# schema_eletrico_PED.net
KiCad netlist of a schematic drawn in EasyEDA
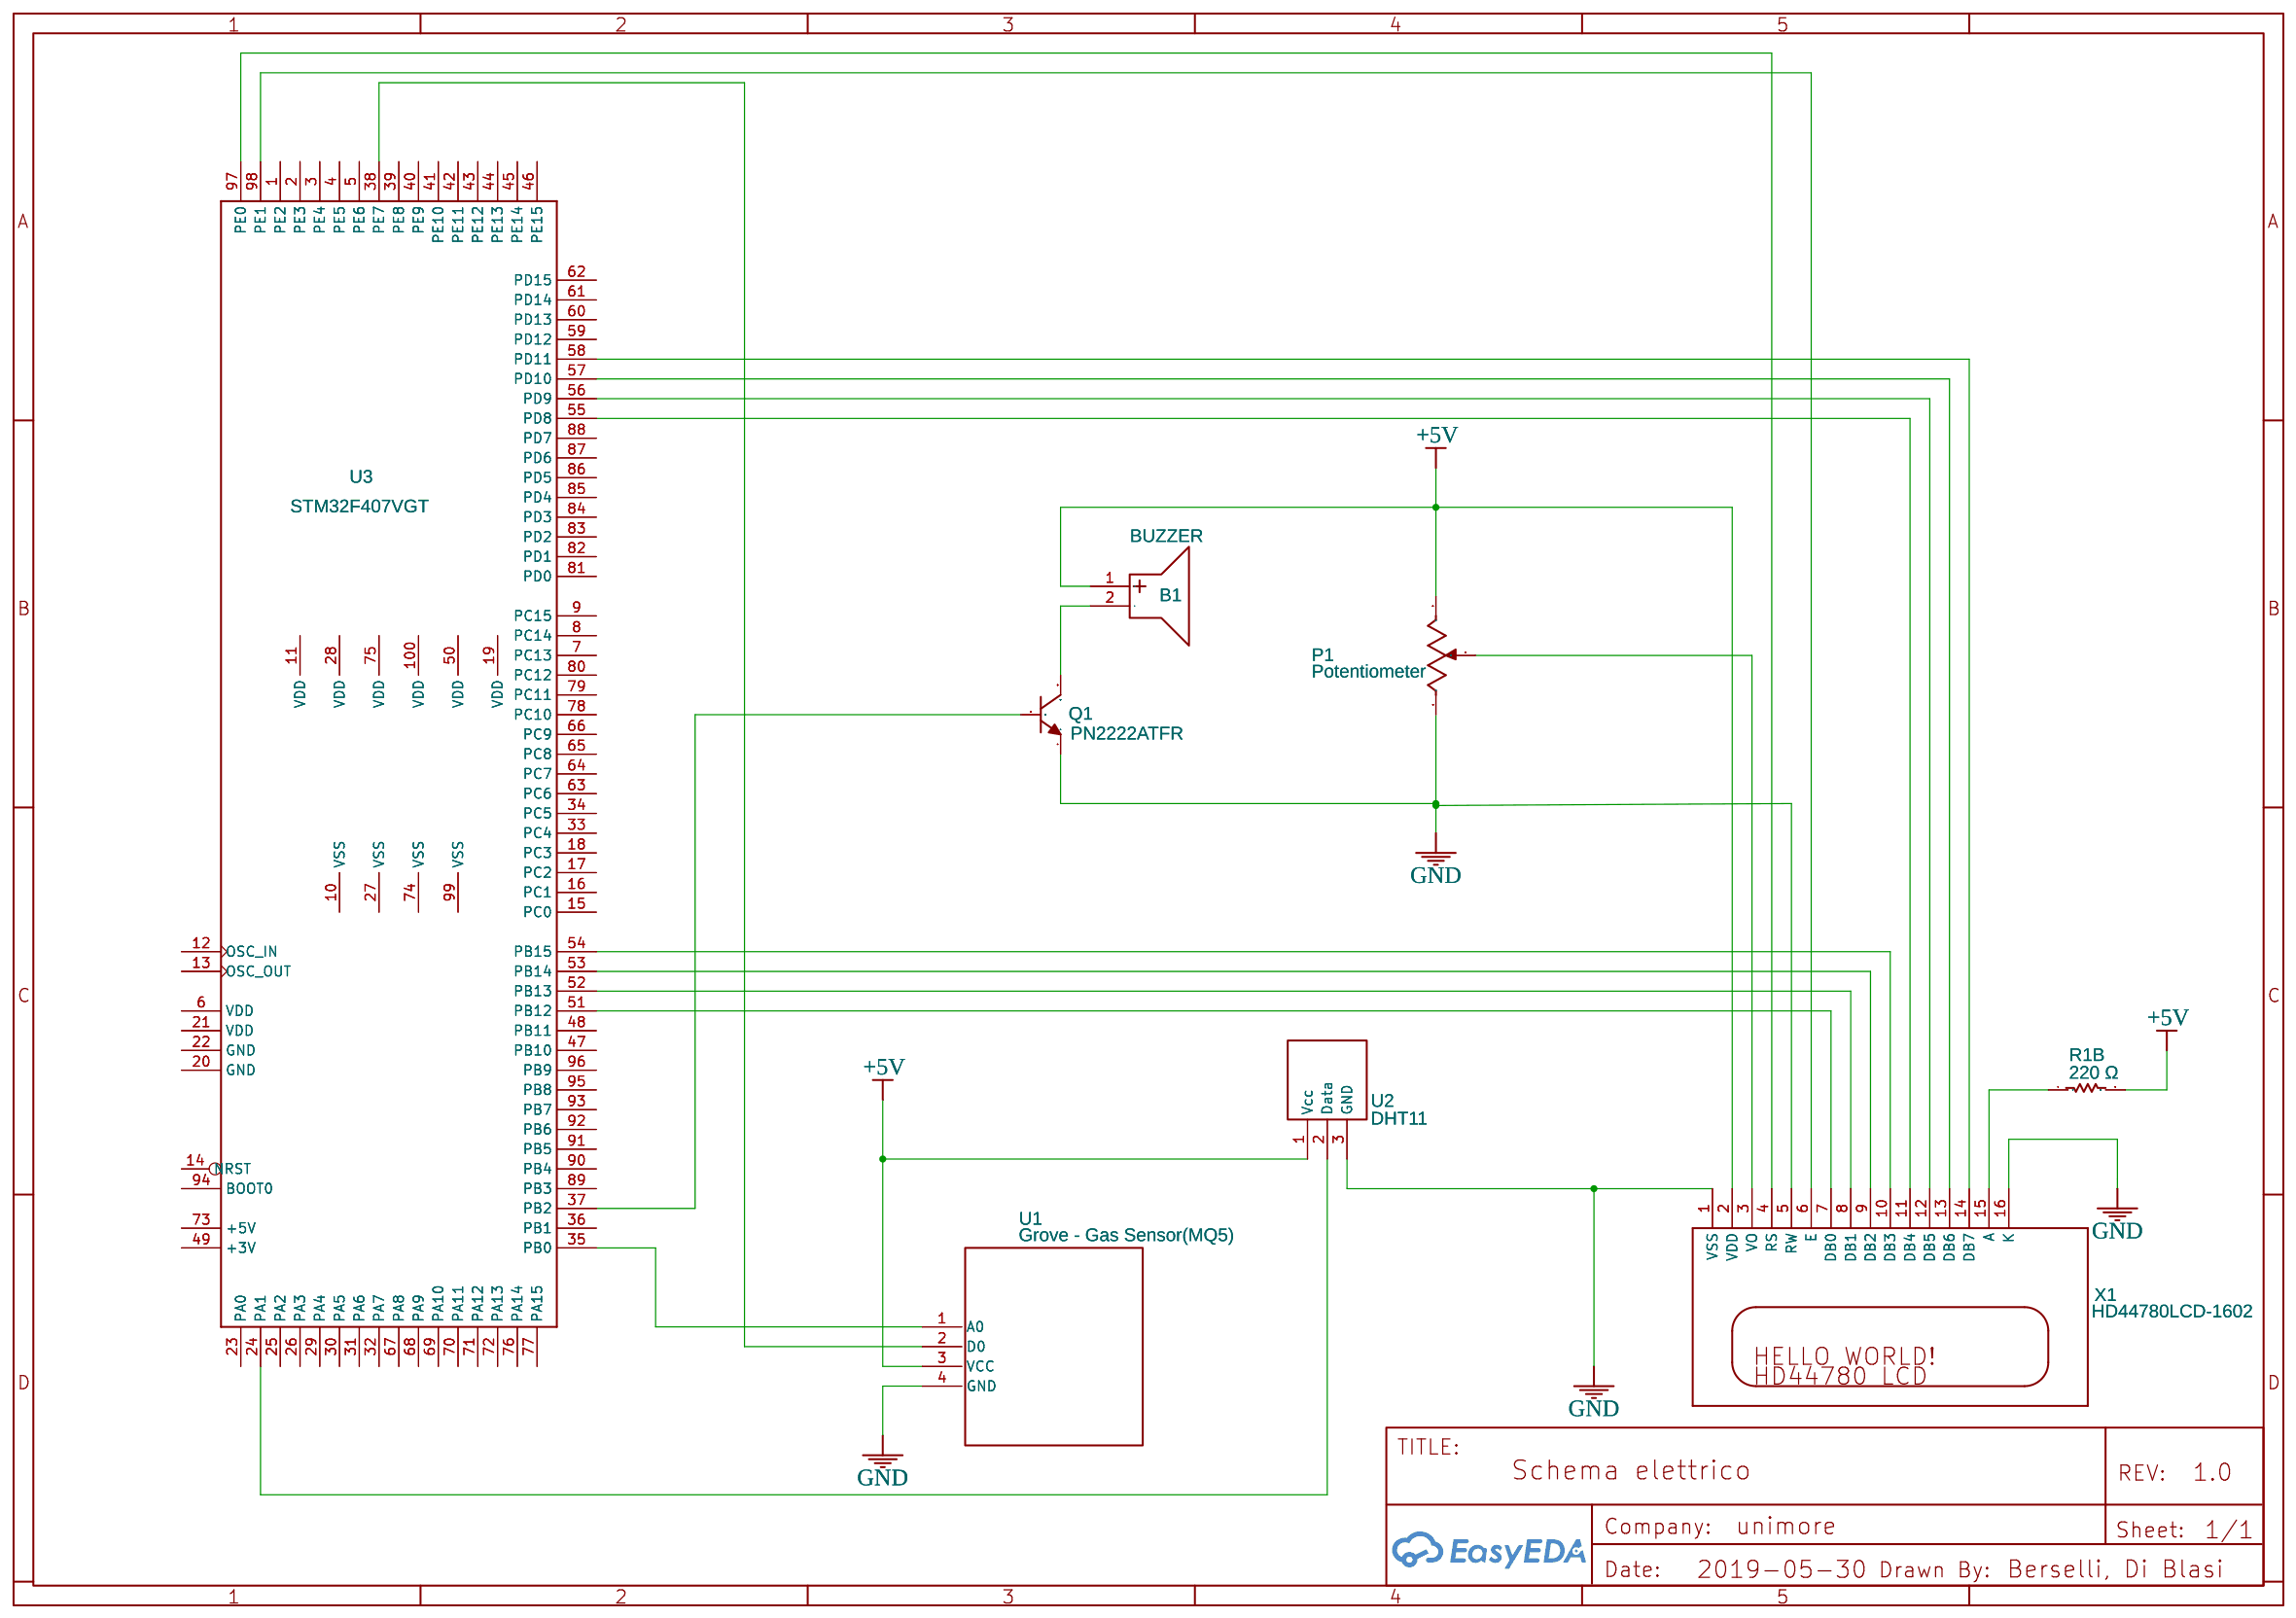
[diagram p0: schematic sheet]

(export (version "E")
  (design (tool "Eeschema 10.0.6"))
  (components
    (comp (ref "B1")
      (value "BUZZER")
      (fields
        (field (name "BOM_Manufacturer Part") "BL-PBZ1209C2003YB-H")
        (field (name "BOM_Supplier Part") "C187885")
      )
      (libsource (lib "") (part "Unknown_575_300"))
    )
    (comp (ref "P1")
      (value "Potentiometer")
      (fields (field (name "BOM_Manufacturer Part") "?"))
      (libsource (lib "") (part "Unknown_720_325"))
    )
    (comp (ref "Q1")
      (value "PN2222ATFR")
      (fields (field (name "BOM_Supplier Part") "C184875"))
      (libsource (lib "") (part "Unknown_520_355"))
    )
    (comp (ref "R1B")
      (value "220 Ω")
      (fields (field (name "BOM_Manufacturer Part") "?") (field (name "BOM_Supplier Part") "P100KHCT-ND"))
      (libsource (lib "") (part "Unknown_1045_545"))
    )
    (comp (ref "U1")
      (value "Grove - Gas Sensor(MQ5)")
      (fields (field (name "BOM_Manufacturer Part") "?") (field (name "BOM_Supplier Part") "undefined"))
      (libsource (lib "") (part "Unknown_515_675"))
    )
    (comp (ref "U2") (value "DHT11") (libsource (lib "") (part "Unknown_725_550")))
    (comp (ref "U3")
      (value "STM32F407VGT")
      (fields (field (name "BOM_Manufacturer Part") "?"))
      (libsource (lib "") (part "Unknown_190_380"))
    )
    (comp (ref "X1")
      (value "HD44780LCD-1602")
      (fields (field (name "BOM_Manufacturer Part") "?"))
      (libsource (lib "") (part "Unknown_950_650"))
    )
  )
  (nets
    (net (code "1") (name "+5V") (class "Default")
      (node (ref "B1") (pin "1") (pinfunction "+_1") (pintype "unspecified"))
      (node (ref "P1") (pin "2") (pinfunction "E_2") (pintype "unspecified"))
      (node (ref "R1B") (pin "2") (pinfunction "2_2") (pintype "passive"))
      (node (ref "U1") (pin "3") (pinfunction "VCC_3") (pintype "unspecified"))
      (node (ref "U2") (pin "1") (pinfunction "Vcc_1") (pintype "unspecified"))
      (node (ref "X1") (pin "2") (pinfunction "VDD_2") (pintype "unspecified"))
    )
    (net (code "2") (name "GND") (class "Default")
      (node (ref "P1") (pin "3") (pinfunction "A_3") (pintype "unspecified"))
      (node (ref "Q1") (pin "1") (pinfunction "E_1") (pintype "unspecified"))
      (node (ref "U1") (pin "4") (pinfunction "GND_4") (pintype "unspecified"))
      (node (ref "U2") (pin "3") (pinfunction "GND_3") (pintype "unspecified"))
      (node (ref "X1") (pin "1") (pinfunction "VSS_1") (pintype "unspecified"))
      (node (ref "X1") (pin "16") (pinfunction "K_16") (pintype "input"))
      (node (ref "X1") (pin "5") (pinfunction "RW_5") (pintype "input"))
    )
    (net (code "3") (name "Net-(B1--)") (class "Default")
      (node (ref "B1") (pin "2") (pinfunction "-_2") (pintype "unspecified"))
      (node (ref "Q1") (pin "3") (pinfunction "C_3") (pintype "unspecified"))
    )
    (net (code "4") (name "Net-(P1-S)") (class "Default")
      (node (ref "P1") (pin "1") (pinfunction "S_1") (pintype "unspecified"))
      (node (ref "X1") (pin "3") (pinfunction "VO_3") (pintype "input"))
    )
    (net (code "5") (name "Net-(Q1-B)") (class "Default")
      (node (ref "Q1") (pin "2") (pinfunction "B_2") (pintype "unspecified"))
      (node (ref "U3") (pin "37") (pinfunction "PB2_37") (pintype "unspecified"))
    )
    (net (code "6") (name "Net-(U1-A0)") (class "Default")
      (node (ref "U1") (pin "1") (pinfunction "A0_1") (pintype "unspecified"))
      (node (ref "U3") (pin "35") (pinfunction "PB0_35") (pintype "unspecified"))
    )
    (net (code "7") (name "Net-(U1-D0)") (class "Default")
      (node (ref "U1") (pin "2") (pinfunction "D0_2") (pintype "unspecified"))
      (node (ref "U3") (pin "38") (pinfunction "PE7_38") (pintype "unspecified"))
    )
    (net (code "8") (name "Net-(U2-Data)") (class "Default")
      (node (ref "U2") (pin "2") (pinfunction "Data_2") (pintype "unspecified"))
      (node (ref "U3") (pin "24") (pinfunction "PA1_24") (pintype "unspecified"))
    )
    (net (code "9") (name "Net-(U3-PB12)") (class "Default")
      (node (ref "U3") (pin "51") (pinfunction "PB12_51") (pintype "unspecified"))
      (node (ref "X1") (pin "7") (pinfunction "DB0_7") (pintype "unspecified"))
    )
    (net (code "10") (name "Net-(U3-PB13)") (class "Default")
      (node (ref "U3") (pin "52") (pinfunction "PB13_52") (pintype "unspecified"))
      (node (ref "X1") (pin "8") (pinfunction "DB1_8") (pintype "unspecified"))
    )
    (net (code "11") (name "Net-(U3-PB14)") (class "Default")
      (node (ref "U3") (pin "53") (pinfunction "PB14_53") (pintype "unspecified"))
      (node (ref "X1") (pin "9") (pinfunction "DB2_9") (pintype "unspecified"))
    )
    (net (code "12") (name "Net-(U3-PB15)") (class "Default")
      (node (ref "U3") (pin "54") (pinfunction "PB15_54") (pintype "unspecified"))
      (node (ref "X1") (pin "10") (pinfunction "DB3_10") (pintype "unspecified"))
    )
    (net (code "13") (name "Net-(U3-PD8)") (class "Default")
      (node (ref "U3") (pin "55") (pinfunction "PD8_55") (pintype "unspecified"))
      (node (ref "X1") (pin "11") (pinfunction "DB4_11") (pintype "unspecified"))
    )
    (net (code "14") (name "Net-(U3-PD9)") (class "Default")
      (node (ref "U3") (pin "56") (pinfunction "PD9_56") (pintype "unspecified"))
      (node (ref "X1") (pin "12") (pinfunction "DB5_12") (pintype "unspecified"))
    )
    (net (code "15") (name "Net-(U3-PD10)") (class "Default")
      (node (ref "U3") (pin "57") (pinfunction "PD10_57") (pintype "unspecified"))
      (node (ref "X1") (pin "13") (pinfunction "DB6_13") (pintype "unspecified"))
    )
    (net (code "16") (name "Net-(U3-PD11)") (class "Default")
      (node (ref "U3") (pin "58") (pinfunction "PD11_58") (pintype "unspecified"))
      (node (ref "X1") (pin "14") (pinfunction "DB7_14") (pintype "unspecified"))
    )
    (net (code "17") (name "Net-(U3-PE0)") (class "Default")
      (node (ref "U3") (pin "97") (pinfunction "PE0_97") (pintype "unspecified"))
      (node (ref "X1") (pin "4") (pinfunction "RS_4") (pintype "input"))
    )
    (net (code "18") (name "Net-(U3-PE1)") (class "Default")
      (node (ref "U3") (pin "98") (pinfunction "PE1_98") (pintype "unspecified"))
      (node (ref "X1") (pin "6") (pinfunction "E_6") (pintype "input"))
    )
    (net (code "19") (name "Net-(X1-A)") (class "Default")
      (node (ref "R1B") (pin "1") (pinfunction "1_1") (pintype "passive"))
      (node (ref "X1") (pin "15") (pinfunction "A_15") (pintype "input"))
    )
    (net (code "20") (name "unconnected-(U3-+3V-Pad49)") (class "Default")
      (node (ref "U3") (pin "49") (pinfunction "+3V_49") (pintype "passive"))
    )
    (net (code "21") (name "unconnected-(U3-+5V-Pad73)") (class "Default")
      (node (ref "U3") (pin "73") (pinfunction "+5V_73") (pintype "passive"))
    )
    (net (code "22") (name "unconnected-(U3-BOOT0-Pad94)") (class "Default")
      (node (ref "U3") (pin "94") (pinfunction "BOOT0_94") (pintype "input"))
    )
    (net (code "23") (name "unconnected-(U3-GND-Pad20)") (class "Default")
      (node (ref "U3") (pin "20") (pinfunction "GND_20") (pintype "passive"))
    )
    (net (code "24") (name "unconnected-(U3-GND-Pad22)") (class "Default")
      (node (ref "U3") (pin "22") (pinfunction "GND_22") (pintype "passive"))
    )
    (net (code "25") (name "unconnected-(U3-NRST-Pad14)") (class "Default")
      (node (ref "U3") (pin "14") (pinfunction "NRST_14") (pintype "unspecified"))
    )
    (net (code "26") (name "unconnected-(U3-OSC_IN-Pad12)") (class "Default")
      (node (ref "U3") (pin "12") (pinfunction "OSC_IN_12") (pintype "unspecified"))
    )
    (net (code "27") (name "unconnected-(U3-OSC_OUT-Pad13)") (class "Default")
      (node (ref "U3") (pin "13") (pinfunction "OSC_OUT_13") (pintype "unspecified"))
    )
    (net (code "28") (name "unconnected-(U3-PA0-Pad23)") (class "Default")
      (node (ref "U3") (pin "23") (pinfunction "PA0_23") (pintype "unspecified"))
    )
    (net (code "29") (name "unconnected-(U3-PA2-Pad25)") (class "Default")
      (node (ref "U3") (pin "25") (pinfunction "PA2_25") (pintype "unspecified"))
    )
    (net (code "30") (name "unconnected-(U3-PA3-Pad26)") (class "Default")
      (node (ref "U3") (pin "26") (pinfunction "PA3_26") (pintype "unspecified"))
    )
    (net (code "31") (name "unconnected-(U3-PA4-Pad29)") (class "Default")
      (node (ref "U3") (pin "29") (pinfunction "PA4_29") (pintype "unspecified"))
    )
    (net (code "32") (name "unconnected-(U3-PA5-Pad30)") (class "Default")
      (node (ref "U3") (pin "30") (pinfunction "PA5_30") (pintype "unspecified"))
    )
    (net (code "33") (name "unconnected-(U3-PA6-Pad31)") (class "Default")
      (node (ref "U3") (pin "31") (pinfunction "PA6_31") (pintype "unspecified"))
    )
    (net (code "34") (name "unconnected-(U3-PA7-Pad32)") (class "Default")
      (node (ref "U3") (pin "32") (pinfunction "PA7_32") (pintype "unspecified"))
    )
    (net (code "35") (name "unconnected-(U3-PA8-Pad67)") (class "Default")
      (node (ref "U3") (pin "67") (pinfunction "PA8_67") (pintype "unspecified"))
    )
    (net (code "36") (name "unconnected-(U3-PA9-Pad68)") (class "Default")
      (node (ref "U3") (pin "68") (pinfunction "PA9_68") (pintype "unspecified"))
    )
    (net (code "37") (name "unconnected-(U3-PA10-Pad69)") (class "Default")
      (node (ref "U3") (pin "69") (pinfunction "PA10_69") (pintype "unspecified"))
    )
    (net (code "38") (name "unconnected-(U3-PA11-Pad70)") (class "Default")
      (node (ref "U3") (pin "70") (pinfunction "PA11_70") (pintype "unspecified"))
    )
    (net (code "39") (name "unconnected-(U3-PA12-Pad71)") (class "Default")
      (node (ref "U3") (pin "71") (pinfunction "PA12_71") (pintype "unspecified"))
    )
    (net (code "40") (name "unconnected-(U3-PA13-Pad72)") (class "Default")
      (node (ref "U3") (pin "72") (pinfunction "PA13_72") (pintype "unspecified"))
    )
    (net (code "41") (name "unconnected-(U3-PA14-Pad76)") (class "Default")
      (node (ref "U3") (pin "76") (pinfunction "PA14_76") (pintype "unspecified"))
    )
    (net (code "42") (name "unconnected-(U3-PA15-Pad77)") (class "Default")
      (node (ref "U3") (pin "77") (pinfunction "PA15_77") (pintype "unspecified"))
    )
    (net (code "43") (name "unconnected-(U3-PB1-Pad36)") (class "Default")
      (node (ref "U3") (pin "36") (pinfunction "PB1_36") (pintype "unspecified"))
    )
    (net (code "44") (name "unconnected-(U3-PB3-Pad89)") (class "Default")
      (node (ref "U3") (pin "89") (pinfunction "PB3_89") (pintype "unspecified"))
    )
    (net (code "45") (name "unconnected-(U3-PB4-Pad90)") (class "Default")
      (node (ref "U3") (pin "90") (pinfunction "PB4_90") (pintype "unspecified"))
    )
    (net (code "46") (name "unconnected-(U3-PB5-Pad91)") (class "Default")
      (node (ref "U3") (pin "91") (pinfunction "PB5_91") (pintype "unspecified"))
    )
    (net (code "47") (name "unconnected-(U3-PB6-Pad92)") (class "Default")
      (node (ref "U3") (pin "92") (pinfunction "PB6_92") (pintype "unspecified"))
    )
    (net (code "48") (name "unconnected-(U3-PB7-Pad93)") (class "Default")
      (node (ref "U3") (pin "93") (pinfunction "PB7_93") (pintype "unspecified"))
    )
    (net (code "49") (name "unconnected-(U3-PB8-Pad95)") (class "Default")
      (node (ref "U3") (pin "95") (pinfunction "PB8_95") (pintype "unspecified"))
    )
    (net (code "50") (name "unconnected-(U3-PB9-Pad96)") (class "Default")
      (node (ref "U3") (pin "96") (pinfunction "PB9_96") (pintype "unspecified"))
    )
    (net (code "51") (name "unconnected-(U3-PB10-Pad47)") (class "Default")
      (node (ref "U3") (pin "47") (pinfunction "PB10_47") (pintype "unspecified"))
    )
    (net (code "52") (name "unconnected-(U3-PB11-Pad48)") (class "Default")
      (node (ref "U3") (pin "48") (pinfunction "PB11_48") (pintype "unspecified"))
    )
    (net (code "53") (name "unconnected-(U3-PC0-Pad15)") (class "Default")
      (node (ref "U3") (pin "15") (pinfunction "PC0_15") (pintype "unspecified"))
    )
    (net (code "54") (name "unconnected-(U3-PC1-Pad16)") (class "Default")
      (node (ref "U3") (pin "16") (pinfunction "PC1_16") (pintype "unspecified"))
    )
    (net (code "55") (name "unconnected-(U3-PC2-Pad17)") (class "Default")
      (node (ref "U3") (pin "17") (pinfunction "PC2_17") (pintype "unspecified"))
    )
    (net (code "56") (name "unconnected-(U3-PC3-Pad18)") (class "Default")
      (node (ref "U3") (pin "18") (pinfunction "PC3_18") (pintype "unspecified"))
    )
    (net (code "57") (name "unconnected-(U3-PC4-Pad33)") (class "Default")
      (node (ref "U3") (pin "33") (pinfunction "PC4_33") (pintype "unspecified"))
    )
    (net (code "58") (name "unconnected-(U3-PC5-Pad34)") (class "Default")
      (node (ref "U3") (pin "34") (pinfunction "PC5_34") (pintype "unspecified"))
    )
    (net (code "59") (name "unconnected-(U3-PC6-Pad63)") (class "Default")
      (node (ref "U3") (pin "63") (pinfunction "PC6_63") (pintype "unspecified"))
    )
    (net (code "60") (name "unconnected-(U3-PC7-Pad64)") (class "Default")
      (node (ref "U3") (pin "64") (pinfunction "PC7_64") (pintype "unspecified"))
    )
    (net (code "61") (name "unconnected-(U3-PC8-Pad65)") (class "Default")
      (node (ref "U3") (pin "65") (pinfunction "PC8_65") (pintype "unspecified"))
    )
    (net (code "62") (name "unconnected-(U3-PC9-Pad66)") (class "Default")
      (node (ref "U3") (pin "66") (pinfunction "PC9_66") (pintype "unspecified"))
    )
    (net (code "63") (name "unconnected-(U3-PC10-Pad78)") (class "Default")
      (node (ref "U3") (pin "78") (pinfunction "PC10_78") (pintype "unspecified"))
    )
    (net (code "64") (name "unconnected-(U3-PC11-Pad79)") (class "Default")
      (node (ref "U3") (pin "79") (pinfunction "PC11_79") (pintype "unspecified"))
    )
    (net (code "65") (name "unconnected-(U3-PC12-Pad80)") (class "Default")
      (node (ref "U3") (pin "80") (pinfunction "PC12_80") (pintype "unspecified"))
    )
    (net (code "66") (name "unconnected-(U3-PC13-Pad7)") (class "Default")
      (node (ref "U3") (pin "7") (pinfunction "PC13_7") (pintype "unspecified"))
    )
    (net (code "67") (name "unconnected-(U3-PC14-Pad8)") (class "Default")
      (node (ref "U3") (pin "8") (pinfunction "PC14_8") (pintype "unspecified"))
    )
    (net (code "68") (name "unconnected-(U3-PC15-Pad9)") (class "Default")
      (node (ref "U3") (pin "9") (pinfunction "PC15_9") (pintype "unspecified"))
    )
    (net (code "69") (name "unconnected-(U3-PD0-Pad81)") (class "Default")
      (node (ref "U3") (pin "81") (pinfunction "PD0_81") (pintype "unspecified"))
    )
    (net (code "70") (name "unconnected-(U3-PD1-Pad82)") (class "Default")
      (node (ref "U3") (pin "82") (pinfunction "PD1_82") (pintype "unspecified"))
    )
    (net (code "71") (name "unconnected-(U3-PD2-Pad83)") (class "Default")
      (node (ref "U3") (pin "83") (pinfunction "PD2_83") (pintype "unspecified"))
    )
    (net (code "72") (name "unconnected-(U3-PD3-Pad84)") (class "Default")
      (node (ref "U3") (pin "84") (pinfunction "PD3_84") (pintype "unspecified"))
    )
    (net (code "73") (name "unconnected-(U3-PD4-Pad85)") (class "Default")
      (node (ref "U3") (pin "85") (pinfunction "PD4_85") (pintype "unspecified"))
    )
    (net (code "74") (name "unconnected-(U3-PD5-Pad86)") (class "Default")
      (node (ref "U3") (pin "86") (pinfunction "PD5_86") (pintype "unspecified"))
    )
    (net (code "75") (name "unconnected-(U3-PD6-Pad87)") (class "Default")
      (node (ref "U3") (pin "87") (pinfunction "PD6_87") (pintype "unspecified"))
    )
    (net (code "76") (name "unconnected-(U3-PD7-Pad88)") (class "Default")
      (node (ref "U3") (pin "88") (pinfunction "PD7_88") (pintype "unspecified"))
    )
    (net (code "77") (name "unconnected-(U3-PD12-Pad59)") (class "Default")
      (node (ref "U3") (pin "59") (pinfunction "PD12_59") (pintype "unspecified"))
    )
    (net (code "78") (name "unconnected-(U3-PD13-Pad60)") (class "Default")
      (node (ref "U3") (pin "60") (pinfunction "PD13_60") (pintype "unspecified"))
    )
    (net (code "79") (name "unconnected-(U3-PD14-Pad61)") (class "Default")
      (node (ref "U3") (pin "61") (pinfunction "PD14_61") (pintype "unspecified"))
    )
    (net (code "80") (name "unconnected-(U3-PD15-Pad62)") (class "Default")
      (node (ref "U3") (pin "62") (pinfunction "PD15_62") (pintype "unspecified"))
    )
    (net (code "81") (name "unconnected-(U3-PE2-Pad1)") (class "Default")
      (node (ref "U3") (pin "1") (pinfunction "PE2_1") (pintype "unspecified"))
    )
    (net (code "82") (name "unconnected-(U3-PE3-Pad2)") (class "Default")
      (node (ref "U3") (pin "2") (pinfunction "PE3_2") (pintype "unspecified"))
    )
    (net (code "83") (name "unconnected-(U3-PE4-Pad3)") (class "Default")
      (node (ref "U3") (pin "3") (pinfunction "PE4_3") (pintype "unspecified"))
    )
    (net (code "84") (name "unconnected-(U3-PE5-Pad4)") (class "Default")
      (node (ref "U3") (pin "4") (pinfunction "PE5_4") (pintype "unspecified"))
    )
    (net (code "85") (name "unconnected-(U3-PE6-Pad5)") (class "Default")
      (node (ref "U3") (pin "5") (pinfunction "PE6_5") (pintype "unspecified"))
    )
    (net (code "86") (name "unconnected-(U3-PE8-Pad39)") (class "Default")
      (node (ref "U3") (pin "39") (pinfunction "PE8_39") (pintype "unspecified"))
    )
    (net (code "87") (name "unconnected-(U3-PE9-Pad40)") (class "Default")
      (node (ref "U3") (pin "40") (pinfunction "PE9_40") (pintype "unspecified"))
    )
    (net (code "88") (name "unconnected-(U3-PE10-Pad41)") (class "Default")
      (node (ref "U3") (pin "41") (pinfunction "PE10_41") (pintype "unspecified"))
    )
    (net (code "89") (name "unconnected-(U3-PE11-Pad42)") (class "Default")
      (node (ref "U3") (pin "42") (pinfunction "PE11_42") (pintype "unspecified"))
    )
    (net (code "90") (name "unconnected-(U3-PE12-Pad43)") (class "Default")
      (node (ref "U3") (pin "43") (pinfunction "PE12_43") (pintype "unspecified"))
    )
    (net (code "91") (name "unconnected-(U3-PE13-Pad44)") (class "Default")
      (node (ref "U3") (pin "44") (pinfunction "PE13_44") (pintype "unspecified"))
    )
    (net (code "92") (name "unconnected-(U3-PE14-Pad45)") (class "Default")
      (node (ref "U3") (pin "45") (pinfunction "PE14_45") (pintype "unspecified"))
    )
    (net (code "93") (name "unconnected-(U3-PE15-Pad46)") (class "Default")
      (node (ref "U3") (pin "46") (pinfunction "PE15_46") (pintype "unspecified"))
    )
    (net (code "94") (name "unconnected-(U3-VDD-Pad6)") (class "Default")
      (node (ref "U3") (pin "6") (pinfunction "VDD_6") (pintype "passive"))
    )
    (net (code "95") (name "unconnected-(U3-VDD-Pad11)") (class "Default")
      (node (ref "U3") (pin "11") (pinfunction "VDD_11") (pintype "passive"))
    )
    (net (code "96") (name "unconnected-(U3-VDD-Pad19)") (class "Default")
      (node (ref "U3") (pin "19") (pinfunction "VDD_19") (pintype "passive"))
    )
    (net (code "97") (name "unconnected-(U3-VDD-Pad21)") (class "Default")
      (node (ref "U3") (pin "21") (pinfunction "VDD_21") (pintype "passive"))
    )
    (net (code "98") (name "unconnected-(U3-VDD-Pad28)") (class "Default")
      (node (ref "U3") (pin "28") (pinfunction "VDD_28") (pintype "passive"))
    )
    (net (code "99") (name "unconnected-(U3-VDD-Pad50)") (class "Default")
      (node (ref "U3") (pin "50") (pinfunction "VDD_50") (pintype "passive"))
    )
    (net (code "100") (name "unconnected-(U3-VDD-Pad75)") (class "Default")
      (node (ref "U3") (pin "75") (pinfunction "VDD_75") (pintype "passive"))
    )
    (net (code "101") (name "unconnected-(U3-VDD-Pad100)") (class "Default")
      (node (ref "U3") (pin "100") (pinfunction "VDD_100") (pintype "passive"))
    )
    (net (code "102") (name "unconnected-(U3-VSS-Pad10)") (class "Default")
      (node (ref "U3") (pin "10") (pinfunction "VSS_10") (pintype "passive"))
    )
    (net (code "103") (name "unconnected-(U3-VSS-Pad27)") (class "Default")
      (node (ref "U3") (pin "27") (pinfunction "VSS_27") (pintype "passive"))
    )
    (net (code "104") (name "unconnected-(U3-VSS-Pad74)") (class "Default")
      (node (ref "U3") (pin "74") (pinfunction "VSS_74") (pintype "passive"))
    )
    (net (code "105") (name "unconnected-(U3-VSS-Pad99)") (class "Default")
      (node (ref "U3") (pin "99") (pinfunction "VSS_99") (pintype "passive"))
    )
  )
)
